# board.net
KiCad netlist of a schematic drawn in EAGLE
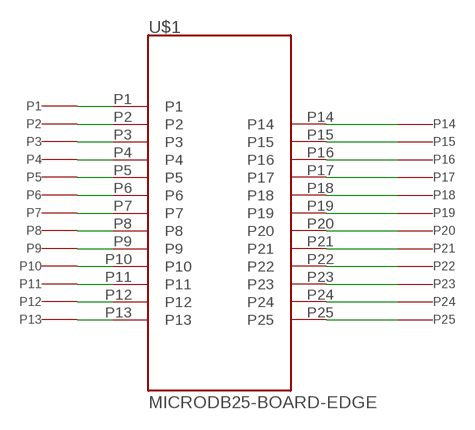
[diagram p0: schematic, sheet 1]

(export (version "E")
  (design (tool "Eeschema 10.0.6"))
  (components
    (comp (ref "P1")
      (value "TP-19MIL")
      (footprint "eagle-import:TP-19MIL")
      (libsource (lib "eagle-import") (part "TP-19MIL"))
    )
    (comp (ref "P2")
      (value "TP-19MIL")
      (footprint "eagle-import:TP-19MIL")
      (libsource (lib "eagle-import") (part "TP-19MIL"))
    )
    (comp (ref "P3")
      (value "TP-19MIL")
      (footprint "eagle-import:TP-19MIL")
      (libsource (lib "eagle-import") (part "TP-19MIL"))
    )
    (comp (ref "P4")
      (value "TP-19MIL")
      (footprint "eagle-import:TP-19MIL")
      (libsource (lib "eagle-import") (part "TP-19MIL"))
    )
    (comp (ref "P5")
      (value "TP-19MIL")
      (footprint "eagle-import:TP-19MIL")
      (libsource (lib "eagle-import") (part "TP-19MIL"))
    )
    (comp (ref "P6")
      (value "TP-19MIL")
      (footprint "eagle-import:TP-19MIL")
      (libsource (lib "eagle-import") (part "TP-19MIL"))
    )
    (comp (ref "P7")
      (value "TP-19MIL")
      (footprint "eagle-import:TP-19MIL")
      (libsource (lib "eagle-import") (part "TP-19MIL"))
    )
    (comp (ref "P8")
      (value "TP-19MIL")
      (footprint "eagle-import:TP-19MIL")
      (libsource (lib "eagle-import") (part "TP-19MIL"))
    )
    (comp (ref "P9")
      (value "TP-19MIL")
      (footprint "eagle-import:TP-19MIL")
      (libsource (lib "eagle-import") (part "TP-19MIL"))
    )
    (comp (ref "P10")
      (value "TP-19MIL")
      (footprint "eagle-import:TP-19MIL")
      (libsource (lib "eagle-import") (part "TP-19MIL"))
    )
    (comp (ref "P11")
      (value "TP-19MIL")
      (footprint "eagle-import:TP-19MIL")
      (libsource (lib "eagle-import") (part "TP-19MIL"))
    )
    (comp (ref "P12")
      (value "TP-19MIL")
      (footprint "eagle-import:TP-19MIL")
      (libsource (lib "eagle-import") (part "TP-19MIL"))
    )
    (comp (ref "P13")
      (value "TP-19MIL")
      (footprint "eagle-import:TP-19MIL")
      (libsource (lib "eagle-import") (part "TP-19MIL"))
    )
    (comp (ref "P14")
      (value "TP-19MIL")
      (footprint "eagle-import:TP-19MIL")
      (libsource (lib "eagle-import") (part "TP-19MIL"))
    )
    (comp (ref "P15")
      (value "TP-19MIL")
      (footprint "eagle-import:TP-19MIL")
      (libsource (lib "eagle-import") (part "TP-19MIL"))
    )
    (comp (ref "P16")
      (value "TP-19MIL")
      (footprint "eagle-import:TP-19MIL")
      (libsource (lib "eagle-import") (part "TP-19MIL"))
    )
    (comp (ref "P17")
      (value "TP-19MIL")
      (footprint "eagle-import:TP-19MIL")
      (libsource (lib "eagle-import") (part "TP-19MIL"))
    )
    (comp (ref "P18")
      (value "TP-19MIL")
      (footprint "eagle-import:TP-19MIL")
      (libsource (lib "eagle-import") (part "TP-19MIL"))
    )
    (comp (ref "P19")
      (value "TP-19MIL")
      (footprint "eagle-import:TP-19MIL")
      (libsource (lib "eagle-import") (part "TP-19MIL"))
    )
    (comp (ref "P20")
      (value "TP-19MIL")
      (footprint "eagle-import:TP-19MIL")
      (libsource (lib "eagle-import") (part "TP-19MIL"))
    )
    (comp (ref "P21")
      (value "TP-19MIL")
      (footprint "eagle-import:TP-19MIL")
      (libsource (lib "eagle-import") (part "TP-19MIL"))
    )
    (comp (ref "P22")
      (value "TP-19MIL")
      (footprint "eagle-import:TP-19MIL")
      (libsource (lib "eagle-import") (part "TP-19MIL"))
    )
    (comp (ref "P23")
      (value "TP-19MIL")
      (footprint "eagle-import:TP-19MIL")
      (libsource (lib "eagle-import") (part "TP-19MIL"))
    )
    (comp (ref "P24")
      (value "TP-19MIL")
      (footprint "eagle-import:TP-19MIL")
      (libsource (lib "eagle-import") (part "TP-19MIL"))
    )
    (comp (ref "P25")
      (value "TP-19MIL")
      (footprint "eagle-import:TP-19MIL")
      (libsource (lib "eagle-import") (part "TP-19MIL"))
    )
    (comp (ref "U$1")
      (value "MICRODB25-BOARD-EDGE")
      (footprint "eagle-import:MICRODB25-BOARD-EDGE")
      (libsource (lib "eagle-import") (part "MICRODB25-BOARD-EDGE"))
    )
  )
  (nets
    (net (code "1") (name "Net-(P1-PadP1)") (class "Default")
      (node (ref "P1") (pin "P1") (pinfunction "P1_P1") (pintype "bidirectional"))
      (node (ref "U$1") (pin "P1") (pinfunction "P1_P1") (pintype "bidirectional"))
    )
    (net (code "2") (name "Net-(P2-PadP1)") (class "Default")
      (node (ref "P2") (pin "P1") (pinfunction "P1_P1") (pintype "bidirectional"))
      (node (ref "U$1") (pin "P2") (pinfunction "P2_P2") (pintype "bidirectional"))
    )
    (net (code "3") (name "Net-(P3-PadP1)") (class "Default")
      (node (ref "P3") (pin "P1") (pinfunction "P1_P1") (pintype "bidirectional"))
      (node (ref "U$1") (pin "P3") (pinfunction "P3_P3") (pintype "bidirectional"))
    )
    (net (code "4") (name "Net-(P4-PadP1)") (class "Default")
      (node (ref "P4") (pin "P1") (pinfunction "P1_P1") (pintype "bidirectional"))
      (node (ref "U$1") (pin "P4") (pinfunction "P4_P4") (pintype "bidirectional"))
    )
    (net (code "5") (name "Net-(P5-PadP1)") (class "Default")
      (node (ref "P5") (pin "P1") (pinfunction "P1_P1") (pintype "bidirectional"))
      (node (ref "U$1") (pin "P5") (pinfunction "P5_P5") (pintype "bidirectional"))
    )
    (net (code "6") (name "Net-(P6-PadP1)") (class "Default")
      (node (ref "P6") (pin "P1") (pinfunction "P1_P1") (pintype "bidirectional"))
      (node (ref "U$1") (pin "P6") (pinfunction "P6_P6") (pintype "bidirectional"))
    )
    (net (code "7") (name "Net-(P7-PadP1)") (class "Default")
      (node (ref "P7") (pin "P1") (pinfunction "P1_P1") (pintype "bidirectional"))
      (node (ref "U$1") (pin "P7") (pinfunction "P7_P7") (pintype "bidirectional"))
    )
    (net (code "8") (name "Net-(P8-PadP1)") (class "Default")
      (node (ref "P8") (pin "P1") (pinfunction "P1_P1") (pintype "bidirectional"))
      (node (ref "U$1") (pin "P8") (pinfunction "P8_P8") (pintype "bidirectional"))
    )
    (net (code "9") (name "Net-(P9-PadP1)") (class "Default")
      (node (ref "P9") (pin "P1") (pinfunction "P1_P1") (pintype "bidirectional"))
      (node (ref "U$1") (pin "P9") (pinfunction "P9_P9") (pintype "bidirectional"))
    )
    (net (code "10") (name "Net-(P10-PadP1)") (class "Default")
      (node (ref "P10") (pin "P1") (pinfunction "P1_P1") (pintype "bidirectional"))
      (node (ref "U$1") (pin "P10") (pinfunction "P10_P10") (pintype "bidirectional"))
    )
    (net (code "11") (name "Net-(P11-PadP1)") (class "Default")
      (node (ref "P11") (pin "P1") (pinfunction "P1_P1") (pintype "bidirectional"))
      (node (ref "U$1") (pin "P11") (pinfunction "P11_P11") (pintype "bidirectional"))
    )
    (net (code "12") (name "Net-(P12-PadP1)") (class "Default")
      (node (ref "P12") (pin "P1") (pinfunction "P1_P1") (pintype "bidirectional"))
      (node (ref "U$1") (pin "P12") (pinfunction "P12_P12") (pintype "bidirectional"))
    )
    (net (code "13") (name "Net-(P13-PadP1)") (class "Default")
      (node (ref "P13") (pin "P1") (pinfunction "P1_P1") (pintype "bidirectional"))
      (node (ref "U$1") (pin "P13") (pinfunction "P13_P13") (pintype "bidirectional"))
    )
    (net (code "14") (name "Net-(P14-PadP1)") (class "Default")
      (node (ref "P14") (pin "P1") (pinfunction "P1_P1") (pintype "bidirectional"))
      (node (ref "U$1") (pin "P14") (pinfunction "P14_P14") (pintype "bidirectional"))
    )
    (net (code "15") (name "Net-(P15-PadP1)") (class "Default")
      (node (ref "P15") (pin "P1") (pinfunction "P1_P1") (pintype "bidirectional"))
      (node (ref "U$1") (pin "P15") (pinfunction "P15_P15") (pintype "bidirectional"))
    )
    (net (code "16") (name "Net-(P16-PadP1)") (class "Default")
      (node (ref "P16") (pin "P1") (pinfunction "P1_P1") (pintype "bidirectional"))
      (node (ref "U$1") (pin "P16") (pinfunction "P16_P16") (pintype "bidirectional"))
    )
    (net (code "17") (name "Net-(P17-PadP1)") (class "Default")
      (node (ref "P17") (pin "P1") (pinfunction "P1_P1") (pintype "bidirectional"))
      (node (ref "U$1") (pin "P17") (pinfunction "P17_P17") (pintype "bidirectional"))
    )
    (net (code "18") (name "Net-(P18-PadP1)") (class "Default")
      (node (ref "P18") (pin "P1") (pinfunction "P1_P1") (pintype "bidirectional"))
      (node (ref "U$1") (pin "P18") (pinfunction "P18_P18") (pintype "bidirectional"))
    )
    (net (code "19") (name "Net-(P19-PadP1)") (class "Default")
      (node (ref "P19") (pin "P1") (pinfunction "P1_P1") (pintype "bidirectional"))
      (node (ref "U$1") (pin "P19") (pinfunction "P19_P19") (pintype "bidirectional"))
    )
    (net (code "20") (name "Net-(P20-PadP1)") (class "Default")
      (node (ref "P20") (pin "P1") (pinfunction "P1_P1") (pintype "bidirectional"))
      (node (ref "U$1") (pin "P20") (pinfunction "P20_P20") (pintype "bidirectional"))
    )
    (net (code "21") (name "Net-(P21-PadP1)") (class "Default")
      (node (ref "P21") (pin "P1") (pinfunction "P1_P1") (pintype "bidirectional"))
      (node (ref "U$1") (pin "P21") (pinfunction "P21_P21") (pintype "bidirectional"))
    )
    (net (code "22") (name "Net-(P22-PadP1)") (class "Default")
      (node (ref "P22") (pin "P1") (pinfunction "P1_P1") (pintype "bidirectional"))
      (node (ref "U$1") (pin "P22") (pinfunction "P22_P22") (pintype "bidirectional"))
    )
    (net (code "23") (name "Net-(P23-PadP1)") (class "Default")
      (node (ref "P23") (pin "P1") (pinfunction "P1_P1") (pintype "bidirectional"))
      (node (ref "U$1") (pin "P23") (pinfunction "P23_P23") (pintype "bidirectional"))
    )
    (net (code "24") (name "Net-(P24-PadP1)") (class "Default")
      (node (ref "P24") (pin "P1") (pinfunction "P1_P1") (pintype "bidirectional"))
      (node (ref "U$1") (pin "P24") (pinfunction "P24_P24") (pintype "bidirectional"))
    )
    (net (code "25") (name "Net-(P25-PadP1)") (class "Default")
      (node (ref "P25") (pin "P1") (pinfunction "P1_P1") (pintype "bidirectional"))
      (node (ref "U$1") (pin "P25") (pinfunction "P25_P25") (pintype "bidirectional"))
    )
  )
)
